# PulseFit.net
KiCad netlist of a schematic drawn in EAGLE
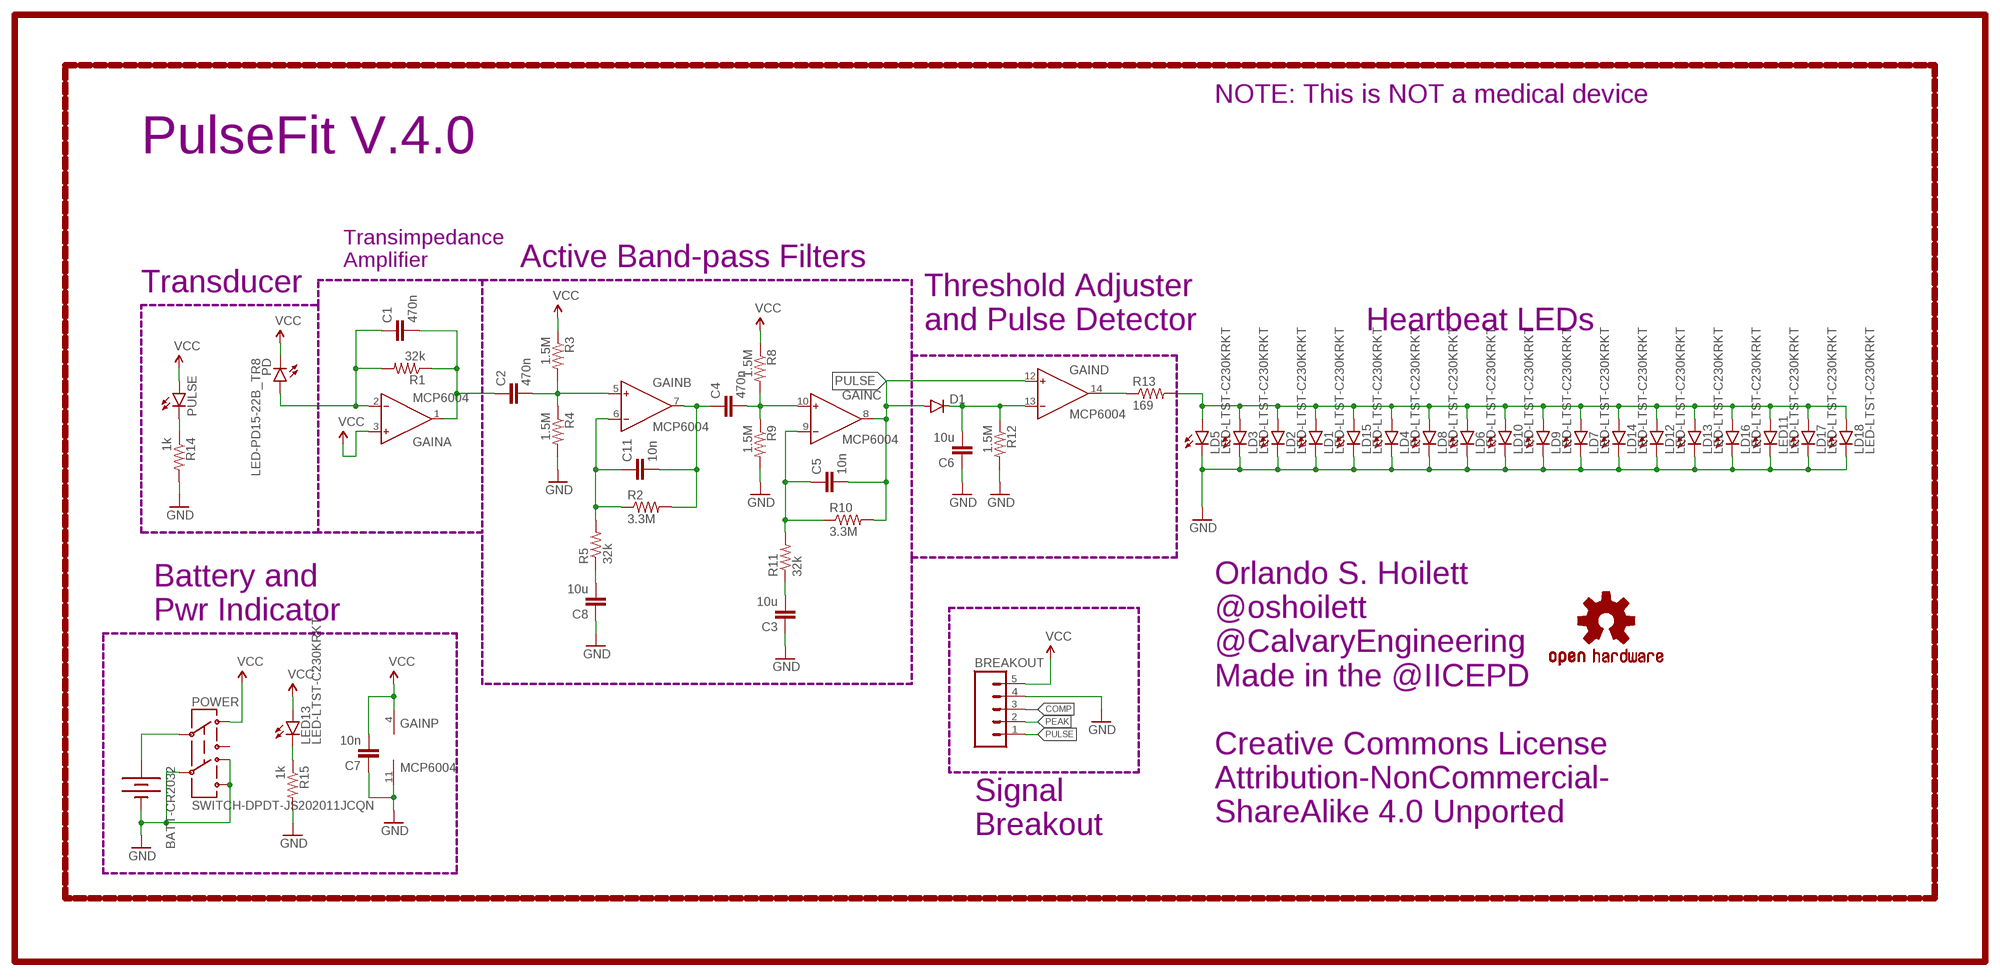
[diagram p0: schematic, sheet 1]

(export (version "E")
  (design (tool "Eeschema 10.0.6"))
  (components
    (comp (ref "BATT-CR2032")
      (value "BATTERY20SMD")
      (footprint "eagle-import:BATTCON_20MM")
      (libsource (lib "eagle-import") (part "BATTERY20SMD"))
    )
    (comp (ref "BREAKOUT")
      (value "M05NO_SILK")
      (footprint "eagle-import:1X05_NO_SILK")
      (libsource (lib "eagle-import") (part "M05NO_SILK"))
    )
    (comp (ref "C1")
      (value "470n")
      (footprint "eagle-import:C0402")
      (libsource (lib "eagle-import") (part "C-EUC0402"))
    )
    (comp (ref "C2")
      (value "470n")
      (footprint "eagle-import:C0402")
      (libsource (lib "eagle-import") (part "C-EUC0402"))
    )
    (comp (ref "C3")
      (value "10u")
      (footprint "eagle-import:C0805")
      (libsource (lib "eagle-import") (part "C-EUC0805"))
    )
    (comp (ref "C4")
      (value "470n")
      (footprint "eagle-import:C0402")
      (libsource (lib "eagle-import") (part "C-EUC0402"))
    )
    (comp (ref "C5")
      (value "10n")
      (footprint "eagle-import:C0402")
      (libsource (lib "eagle-import") (part "C-EUC0402"))
    )
    (comp (ref "C6")
      (value "10u")
      (footprint "eagle-import:C0805")
      (libsource (lib "eagle-import") (part "C-EUC0805"))
    )
    (comp (ref "C7")
      (value "10n")
      (footprint "eagle-import:C0402")
      (libsource (lib "eagle-import") (part "C-EUC0402"))
    )
    (comp (ref "C8")
      (value "10u")
      (footprint "eagle-import:C0805")
      (libsource (lib "eagle-import") (part "C-EUC0805"))
    )
    (comp (ref "C11")
      (value "10n")
      (footprint "eagle-import:C0402")
      (libsource (lib "eagle-import") (part "C-EUC0402"))
    )
    (comp (ref "D1")
      (value "250mA/100V")
      (footprint "eagle-import:SOD-323")
      (libsource (lib "eagle-import") (part "DIODEBAS16"))
    )
    (comp (ref "GAIN")
      (value "MCP6004")
      (footprint "eagle-import:TSSOP14")
      (fields (field (name "MF") "ALTERA CORPORATION") (field (name "MPN") "AD8609ARUZ"))
      (libsource (lib "eagle-import") (part "AD8609RU"))
    )
    (comp (ref "LD1")
      (value "LED-LTST-C230KRKT")
      (footprint "eagle-import:LED-1206-BOTTOM")
      (libsource (lib "eagle-import") (part "LED-LTST-C230KRKT"))
    )
    (comp (ref "LD2")
      (value "LED-LTST-C230KRKT")
      (footprint "eagle-import:LED-1206-BOTTOM")
      (libsource (lib "eagle-import") (part "LED-LTST-C230KRKT"))
    )
    (comp (ref "LD3")
      (value "LED-LTST-C230KRKT")
      (footprint "eagle-import:LED-1206-BOTTOM")
      (libsource (lib "eagle-import") (part "LED-LTST-C230KRKT"))
    )
    (comp (ref "LD4")
      (value "LED-LTST-C230KRKT")
      (footprint "eagle-import:LED-1206-BOTTOM")
      (libsource (lib "eagle-import") (part "LED-LTST-C230KRKT"))
    )
    (comp (ref "LD5")
      (value "LED-LTST-C230KRKT")
      (footprint "eagle-import:LED-1206-BOTTOM")
      (libsource (lib "eagle-import") (part "LED-LTST-C230KRKT"))
    )
    (comp (ref "LD6")
      (value "LED-LTST-C230KRKT")
      (footprint "eagle-import:LED-1206-BOTTOM")
      (libsource (lib "eagle-import") (part "LED-LTST-C230KRKT"))
    )
    (comp (ref "LD7")
      (value "LED-LTST-C230KRKT")
      (footprint "eagle-import:LED-1206-BOTTOM")
      (libsource (lib "eagle-import") (part "LED-LTST-C230KRKT"))
    )
    (comp (ref "LD8")
      (value "LED-LTST-C230KRKT")
      (footprint "eagle-import:LED-1206-BOTTOM")
      (libsource (lib "eagle-import") (part "LED-LTST-C230KRKT"))
    )
    (comp (ref "LD9")
      (value "LED-LTST-C230KRKT")
      (footprint "eagle-import:LED-1206-BOTTOM")
      (libsource (lib "eagle-import") (part "LED-LTST-C230KRKT"))
    )
    (comp (ref "LD10")
      (value "LED-LTST-C230KRKT")
      (footprint "eagle-import:LED-1206-BOTTOM")
      (libsource (lib "eagle-import") (part "LED-LTST-C230KRKT"))
    )
    (comp (ref "LD12")
      (value "LED-LTST-C230KRKT")
      (footprint "eagle-import:LED-1206-BOTTOM")
      (libsource (lib "eagle-import") (part "LED-LTST-C230KRKT"))
    )
    (comp (ref "LD13")
      (value "LED-LTST-C230KRKT")
      (footprint "eagle-import:LED-1206-BOTTOM")
      (libsource (lib "eagle-import") (part "LED-LTST-C230KRKT"))
    )
    (comp (ref "LD14")
      (value "LED-LTST-C230KRKT")
      (footprint "eagle-import:LED-1206-BOTTOM")
      (libsource (lib "eagle-import") (part "LED-LTST-C230KRKT"))
    )
    (comp (ref "LD15")
      (value "LED-LTST-C230KRKT")
      (footprint "eagle-import:LED-1206-BOTTOM")
      (libsource (lib "eagle-import") (part "LED-LTST-C230KRKT"))
    )
    (comp (ref "LD16")
      (value "LED-LTST-C230KRKT")
      (footprint "eagle-import:LED-1206-BOTTOM")
      (libsource (lib "eagle-import") (part "LED-LTST-C230KRKT"))
    )
    (comp (ref "LD17")
      (value "LED-LTST-C230KRKT")
      (footprint "eagle-import:LED-1206-BOTTOM")
      (libsource (lib "eagle-import") (part "LED-LTST-C230KRKT"))
    )
    (comp (ref "LD18")
      (value "LED-LTST-C230KRKT")
      (footprint "eagle-import:LED-1206-BOTTOM")
      (libsource (lib "eagle-import") (part "LED-LTST-C230KRKT"))
    )
    (comp (ref "LED11")
      (value "LED-LTST-C230KRKT")
      (footprint "eagle-import:LED-1206-BOTTOM")
      (libsource (lib "eagle-import") (part "LED-LTST-C230KRKT"))
    )
    (comp (ref "LED13")
      (value "LED-LTST-C230KRKT")
      (footprint "eagle-import:LED-1206-BOTTOM")
      (libsource (lib "eagle-import") (part "LED-LTST-C230KRKT"))
    )
    (comp (ref "LOGO1")
      (value "OSHW-LOGOS")
      (footprint "eagle-import:OSHW-LOGO-S")
      (libsource (lib "eagle-import") (part "OSHW-LOGOS"))
    )
    (comp (ref "PD")
      (value "LED-PD15-22B_TR8")
      (footprint "eagle-import:LED-PD15-22B_TR8")
      (libsource (lib "eagle-import") (part "LED-PD15-22B_TR8"))
    )
    (comp (ref "POWER")
      (value "SWITCH-DPDT-JS202011JCQN")
      (footprint "eagle-import:J-LEAD")
      (libsource (lib "eagle-import") (part "SWITCH-DPDT-JS202011JCQN"))
    )
    (comp (ref "PULSE")
      (value "LED0603")
      (footprint "eagle-import:LED-0603")
      (libsource (lib "eagle-import") (part "LED0603"))
    )
    (comp (ref "R1")
      (value "32k")
      (footprint "eagle-import:R0402")
      (libsource (lib "eagle-import") (part "R-US_R0402"))
    )
    (comp (ref "R2")
      (value "3.3M")
      (footprint "eagle-import:R0402")
      (libsource (lib "eagle-import") (part "R-US_R0402"))
    )
    (comp (ref "R3")
      (value "1.5M")
      (footprint "eagle-import:R0402")
      (libsource (lib "eagle-import") (part "R-US_R0402"))
    )
    (comp (ref "R4")
      (value "1.5M")
      (footprint "eagle-import:R0402")
      (libsource (lib "eagle-import") (part "R-US_R0402"))
    )
    (comp (ref "R5")
      (value "32k")
      (footprint "eagle-import:R0402")
      (libsource (lib "eagle-import") (part "R-US_R0402"))
    )
    (comp (ref "R8")
      (value "1.5M")
      (footprint "eagle-import:R0402")
      (libsource (lib "eagle-import") (part "R-US_R0402"))
    )
    (comp (ref "R9")
      (value "1.5M")
      (footprint "eagle-import:R0402")
      (libsource (lib "eagle-import") (part "R-US_R0402"))
    )
    (comp (ref "R10")
      (value "3.3M")
      (footprint "eagle-import:R0402")
      (libsource (lib "eagle-import") (part "R-US_R0402"))
    )
    (comp (ref "R11")
      (value "32k")
      (footprint "eagle-import:R0402")
      (libsource (lib "eagle-import") (part "R-US_R0402"))
    )
    (comp (ref "R12")
      (value "1.5M")
      (footprint "eagle-import:R0402")
      (libsource (lib "eagle-import") (part "R-US_R0402"))
    )
    (comp (ref "R13")
      (value "169")
      (footprint "eagle-import:R0402")
      (libsource (lib "eagle-import") (part "R-US_R0402"))
    )
    (comp (ref "R14")
      (value "1k")
      (footprint "eagle-import:R0402")
      (libsource (lib "eagle-import") (part "R-US_R0402"))
    )
    (comp (ref "R15")
      (value "1k")
      (footprint "eagle-import:R0402")
      (libsource (lib "eagle-import") (part "R-US_R0402"))
    )
  )
  (nets
    (net (code "1") (name "COMP") (class "Default")
      (node (ref "BREAKOUT") (pin "3") (pinfunction "3_3") (pintype "passive"))
      (node (ref "GAIN") (pin "14") (pinfunction "OUT_14") (pintype "output"))
      (node (ref "R13") (pin "1") (pinfunction "1_1") (pintype "passive"))
    )
    (net (code "2") (name "GND") (class "Default")
      (node (ref "BATT-CR2032") (pin "2") (pinfunction "-_2") (pintype "power_in"))
      (node (ref "BREAKOUT") (pin "4") (pinfunction "4_4") (pintype "passive"))
      (node (ref "C3") (pin "1") (pinfunction "1_1") (pintype "passive"))
      (node (ref "C6") (pin "1") (pinfunction "1_1") (pintype "passive"))
      (node (ref "C7") (pin "1") (pinfunction "1_1") (pintype "passive"))
      (node (ref "C8") (pin "1") (pinfunction "1_1") (pintype "passive"))
      (node (ref "GAIN") (pin "11") (pinfunction "V-_11") (pintype "power_in"))
      (node (ref "LD1") (pin "C") (pinfunction "C_C") (pintype "passive"))
      (node (ref "LD10") (pin "C") (pinfunction "C_C") (pintype "passive"))
      (node (ref "LD12") (pin "C") (pinfunction "C_C") (pintype "passive"))
      (node (ref "LD13") (pin "C") (pinfunction "C_C") (pintype "passive"))
      (node (ref "LD14") (pin "C") (pinfunction "C_C") (pintype "passive"))
      (node (ref "LD15") (pin "C") (pinfunction "C_C") (pintype "passive"))
      (node (ref "LD16") (pin "C") (pinfunction "C_C") (pintype "passive"))
      (node (ref "LD17") (pin "C") (pinfunction "C_C") (pintype "passive"))
      (node (ref "LD18") (pin "C") (pinfunction "C_C") (pintype "passive"))
      (node (ref "LD2") (pin "C") (pinfunction "C_C") (pintype "passive"))
      (node (ref "LD3") (pin "C") (pinfunction "C_C") (pintype "passive"))
      (node (ref "LD4") (pin "C") (pinfunction "C_C") (pintype "passive"))
      (node (ref "LD5") (pin "C") (pinfunction "C_C") (pintype "passive"))
      (node (ref "LD6") (pin "C") (pinfunction "C_C") (pintype "passive"))
      (node (ref "LD7") (pin "C") (pinfunction "C_C") (pintype "passive"))
      (node (ref "LD8") (pin "C") (pinfunction "C_C") (pintype "passive"))
      (node (ref "LD9") (pin "C") (pinfunction "C_C") (pintype "passive"))
      (node (ref "LED11") (pin "C") (pinfunction "C_C") (pintype "passive"))
      (node (ref "POWER") (pin "4") (pinfunction "4_4") (pintype "bidirectional"))
      (node (ref "POWER") (pin "5") (pinfunction "5_5") (pintype "bidirectional"))
      (node (ref "POWER") (pin "6") (pinfunction "6_6") (pintype "bidirectional"))
      (node (ref "R12") (pin "2") (pinfunction "2_2") (pintype "passive"))
      (node (ref "R14") (pin "2") (pinfunction "2_2") (pintype "passive"))
      (node (ref "R15") (pin "2") (pinfunction "2_2") (pintype "passive"))
      (node (ref "R4") (pin "2") (pinfunction "2_2") (pintype "passive"))
      (node (ref "R9") (pin "2") (pinfunction "2_2") (pintype "passive"))
    )
    (net (code "3") (name "Net-(BATT-CR2032-+)") (class "Default")
      (node (ref "BATT-CR2032") (pin "1") (pinfunction "+_1") (pintype "power_in"))
      (node (ref "POWER") (pin "2") (pinfunction "2_2") (pintype "bidirectional"))
    )
    (net (code "4") (name "Net-(C3-Pad2)") (class "Default")
      (node (ref "C3") (pin "2") (pinfunction "2_2") (pintype "passive"))
      (node (ref "R11") (pin "1") (pinfunction "1_1") (pintype "passive"))
    )
    (net (code "5") (name "Net-(C8-Pad2)") (class "Default")
      (node (ref "C8") (pin "2") (pinfunction "2_2") (pintype "passive"))
      (node (ref "R5") (pin "1") (pinfunction "1_1") (pintype "passive"))
    )
    (net (code "6") (name "Net-(GAINA-IN-)") (class "Default")
      (node (ref "C1") (pin "1") (pinfunction "1_1") (pintype "passive"))
      (node (ref "GAIN") (pin "2") (pinfunction "IN-_2") (pintype "input"))
      (node (ref "PD") (pin "A-1") (pinfunction "A_A-1") (pintype "passive"))
      (node (ref "PD") (pin "A-2") (pinfunction "A_A-2") (pintype "passive"))
      (node (ref "R1") (pin "2") (pinfunction "2_2") (pintype "passive"))
    )
    (net (code "7") (name "Net-(GAINA-OUT)") (class "Default")
      (node (ref "C1") (pin "2") (pinfunction "2_2") (pintype "passive"))
      (node (ref "C2") (pin "1") (pinfunction "1_1") (pintype "passive"))
      (node (ref "GAIN") (pin "1") (pinfunction "OUT_1") (pintype "output"))
      (node (ref "R1") (pin "1") (pinfunction "1_1") (pintype "passive"))
    )
    (net (code "8") (name "Net-(GAINB-IN+)") (class "Default")
      (node (ref "C2") (pin "2") (pinfunction "2_2") (pintype "passive"))
      (node (ref "GAIN") (pin "5") (pinfunction "IN+_5") (pintype "input"))
      (node (ref "R3") (pin "2") (pinfunction "2_2") (pintype "passive"))
      (node (ref "R4") (pin "1") (pinfunction "1_1") (pintype "passive"))
    )
    (net (code "9") (name "Net-(GAINB-IN-)") (class "Default")
      (node (ref "C11") (pin "1") (pinfunction "1_1") (pintype "passive"))
      (node (ref "GAIN") (pin "6") (pinfunction "IN-_6") (pintype "input"))
      (node (ref "R2") (pin "1") (pinfunction "1_1") (pintype "passive"))
      (node (ref "R5") (pin "2") (pinfunction "2_2") (pintype "passive"))
    )
    (net (code "10") (name "Net-(GAINB-OUT)") (class "Default")
      (node (ref "C11") (pin "2") (pinfunction "2_2") (pintype "passive"))
      (node (ref "C4") (pin "1") (pinfunction "1_1") (pintype "passive"))
      (node (ref "GAIN") (pin "7") (pinfunction "OUT_7") (pintype "output"))
      (node (ref "R2") (pin "2") (pinfunction "2_2") (pintype "passive"))
    )
    (net (code "11") (name "Net-(GAINC-IN+)") (class "Default")
      (node (ref "C4") (pin "2") (pinfunction "2_2") (pintype "passive"))
      (node (ref "GAIN") (pin "10") (pinfunction "IN+_10") (pintype "input"))
      (node (ref "R8") (pin "2") (pinfunction "2_2") (pintype "passive"))
      (node (ref "R9") (pin "1") (pinfunction "1_1") (pintype "passive"))
    )
    (net (code "12") (name "Net-(GAINC-IN-)") (class "Default")
      (node (ref "C5") (pin "1") (pinfunction "1_1") (pintype "passive"))
      (node (ref "GAIN") (pin "9") (pinfunction "IN-_9") (pintype "input"))
      (node (ref "R10") (pin "1") (pinfunction "1_1") (pintype "passive"))
      (node (ref "R11") (pin "2") (pinfunction "2_2") (pintype "passive"))
    )
    (net (code "13") (name "Net-(LD1-PadA)") (class "Default")
      (node (ref "LD1") (pin "A") (pinfunction "A_A") (pintype "passive"))
      (node (ref "LD10") (pin "A") (pinfunction "A_A") (pintype "passive"))
      (node (ref "LD12") (pin "A") (pinfunction "A_A") (pintype "passive"))
      (node (ref "LD13") (pin "A") (pinfunction "A_A") (pintype "passive"))
      (node (ref "LD14") (pin "A") (pinfunction "A_A") (pintype "passive"))
      (node (ref "LD15") (pin "A") (pinfunction "A_A") (pintype "passive"))
      (node (ref "LD16") (pin "A") (pinfunction "A_A") (pintype "passive"))
      (node (ref "LD17") (pin "A") (pinfunction "A_A") (pintype "passive"))
      (node (ref "LD18") (pin "A") (pinfunction "A_A") (pintype "passive"))
      (node (ref "LD2") (pin "A") (pinfunction "A_A") (pintype "passive"))
      (node (ref "LD3") (pin "A") (pinfunction "A_A") (pintype "passive"))
      (node (ref "LD4") (pin "A") (pinfunction "A_A") (pintype "passive"))
      (node (ref "LD5") (pin "A") (pinfunction "A_A") (pintype "passive"))
      (node (ref "LD6") (pin "A") (pinfunction "A_A") (pintype "passive"))
      (node (ref "LD7") (pin "A") (pinfunction "A_A") (pintype "passive"))
      (node (ref "LD8") (pin "A") (pinfunction "A_A") (pintype "passive"))
      (node (ref "LD9") (pin "A") (pinfunction "A_A") (pintype "passive"))
      (node (ref "LED11") (pin "A") (pinfunction "A_A") (pintype "passive"))
      (node (ref "R13") (pin "2") (pinfunction "2_2") (pintype "passive"))
    )
    (net (code "14") (name "Net-(LED13-PadC)") (class "Default")
      (node (ref "LED13") (pin "C") (pinfunction "C_C") (pintype "passive"))
      (node (ref "R15") (pin "1") (pinfunction "1_1") (pintype "passive"))
    )
    (net (code "15") (name "Net-(PULSE-PadC)") (class "Default")
      (node (ref "PULSE") (pin "C") (pinfunction "C_C") (pintype "passive"))
      (node (ref "R14") (pin "1") (pinfunction "1_1") (pintype "passive"))
    )
    (net (code "16") (name "PEAK") (class "Default")
      (node (ref "BREAKOUT") (pin "2") (pinfunction "2_2") (pintype "passive"))
      (node (ref "C6") (pin "2") (pinfunction "2_2") (pintype "passive"))
      (node (ref "D1") (pin "C") (pinfunction "C_C") (pintype "passive"))
      (node (ref "GAIN") (pin "13") (pinfunction "IN-_13") (pintype "input"))
      (node (ref "R12") (pin "1") (pinfunction "1_1") (pintype "passive"))
    )
    (net (code "17") (name "PULSE") (class "Default")
      (node (ref "BREAKOUT") (pin "1") (pinfunction "1_1") (pintype "passive"))
      (node (ref "C5") (pin "2") (pinfunction "2_2") (pintype "passive"))
      (node (ref "D1") (pin "A") (pinfunction "A_A") (pintype "passive"))
      (node (ref "GAIN") (pin "12") (pinfunction "IN+_12") (pintype "input"))
      (node (ref "GAIN") (pin "8") (pinfunction "OUT_8") (pintype "output"))
      (node (ref "R10") (pin "2") (pinfunction "2_2") (pintype "passive"))
    )
    (net (code "18") (name "VCC") (class "Default")
      (node (ref "BREAKOUT") (pin "5") (pinfunction "5_5") (pintype "passive"))
      (node (ref "C7") (pin "2") (pinfunction "2_2") (pintype "passive"))
      (node (ref "GAIN") (pin "3") (pinfunction "IN+_3") (pintype "input"))
      (node (ref "GAIN") (pin "4") (pinfunction "V+_4") (pintype "power_in"))
      (node (ref "LED13") (pin "A") (pinfunction "A_A") (pintype "passive"))
      (node (ref "PD") (pin "C-1") (pinfunction "C_C-1") (pintype "passive"))
      (node (ref "PD") (pin "C-2") (pinfunction "C_C-2") (pintype "passive"))
      (node (ref "POWER") (pin "1") (pinfunction "1_1") (pintype "bidirectional"))
      (node (ref "PULSE") (pin "A") (pinfunction "A_A") (pintype "passive"))
      (node (ref "R3") (pin "1") (pinfunction "1_1") (pintype "passive"))
      (node (ref "R8") (pin "1") (pinfunction "1_1") (pintype "passive"))
    )
    (net (code "19") (name "unconnected-(POWER-Pad3)") (class "Default")
      (node (ref "POWER") (pin "3") (pinfunction "3_3") (pintype "bidirectional"))
    )
  )
)
